# blackfin_b_flash_jtag_serial.net
KiCad netlist of a schematic drawn in Altium Designer
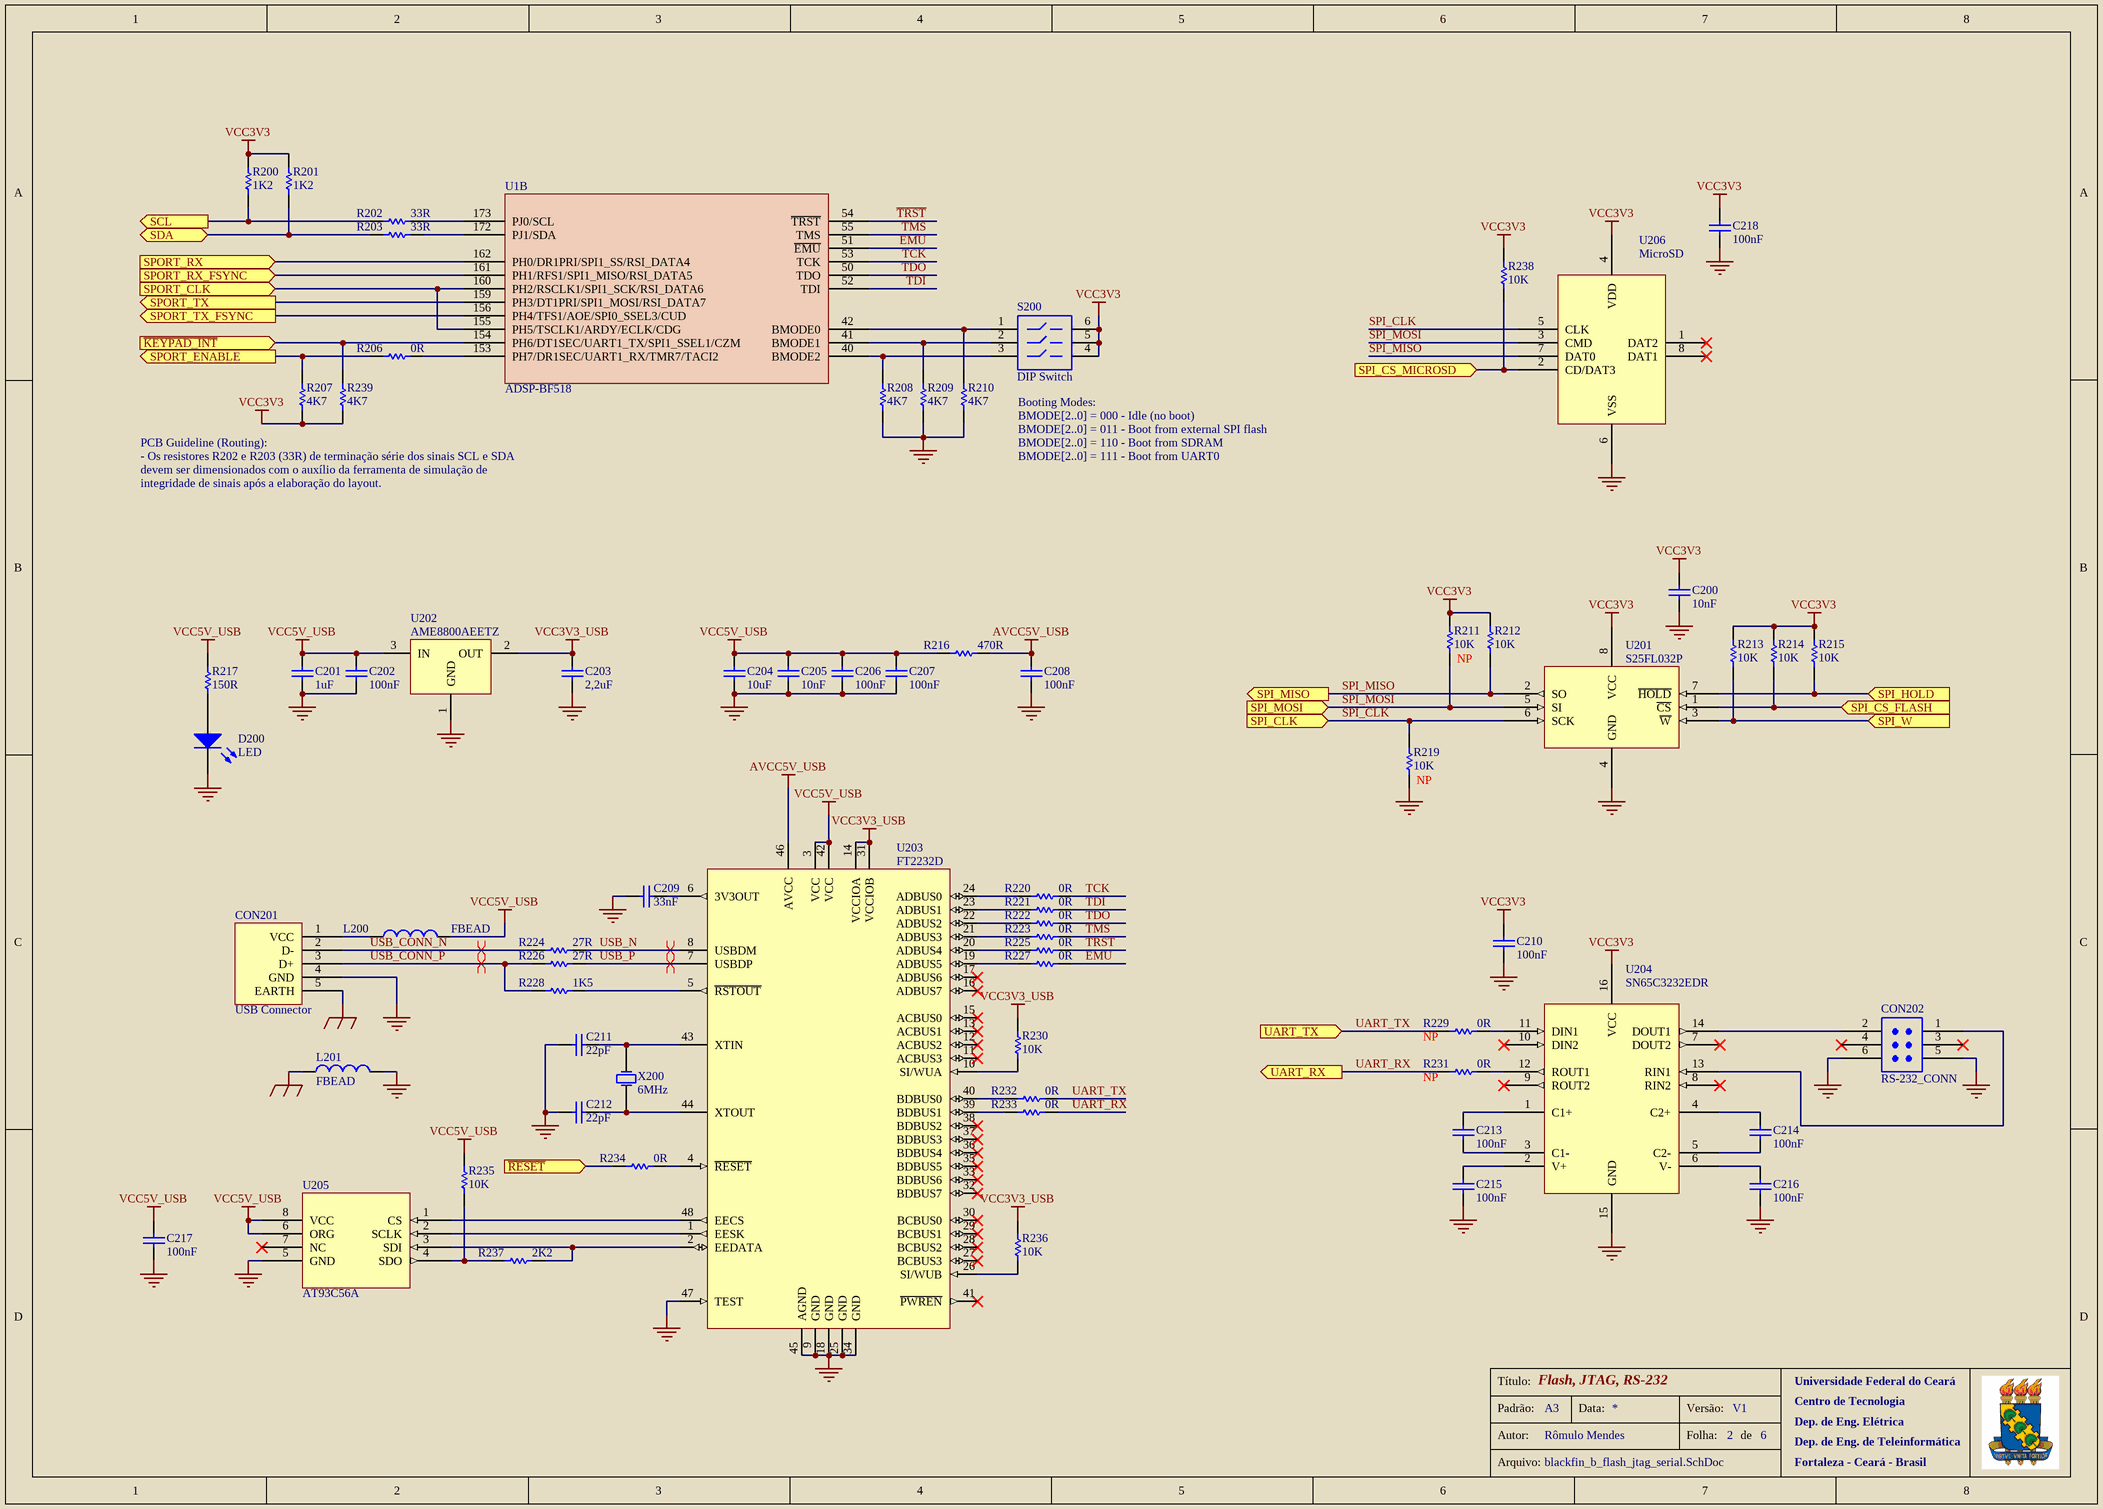
[diagram p0: blackfin_b_flash_jtag_serial.SchDoc]

(export (version "E")
  (design (tool "Eeschema 10.0.6"))
  (components
    (comp (ref "C200")
      (value "10nF")
      (footprint "blackfin_pcblib:C_0603")
      (fields
        (field (name "EVENDORPART#") "77-VJ0603Y103KXAPBC")
        (field (name "MANUFACTURER") "Vishay/Vitramon")
        (field (name "PART#") "VJ0603Y103KXAPW1BC")
      )
      (libsource (lib "blackfin_schlib") (part "Capacitor"))
    )
    (comp (ref "C201")
      (value "1uF")
      (footprint "blackfin_pcblib:C_0603")
      (fields
        (field (name "EVENDORPART#") "81-GRM188F51E105ZA12")
        (field (name "MANUFACTURER") "Murata")
        (field (name "PART#") "GRM188F51E105ZA12D")
      )
      (libsource (lib "blackfin_schlib") (part "Capacitor"))
    )
    (comp (ref "C202")
      (value "100nF")
      (footprint "blackfin_pcblib:C_0603")
      (fields
        (field (name "EVENDORPART#") "81-GRM188R71E104KA01")
        (field (name "MANUFACTURER") "Murata")
        (field (name "PART#") "GRM188R71E104KA01J")
      )
      (libsource (lib "blackfin_schlib") (part "Capacitor"))
    )
    (comp (ref "C203")
      (value "2,2uF")
      (footprint "blackfin_pcblib:C_0603")
      (fields
        (field (name "EVENDORPART#") "81-GRM188F51A225ZE01")
        (field (name "MANUFACTURER") "Murata")
        (field (name "PART#") "GRM188F51A225ZE01D")
      )
      (libsource (lib "blackfin_schlib") (part "Capacitor"))
    )
    (comp (ref "C204")
      (value "10uF")
      (footprint "blackfin_pcblib:C_0805")
      (fields
        (field (name "EVENDORPART#") "810-C2012Y5V1C106Z")
        (field (name "MANUFACTURER") "TDK")
        (field (name "PART#") "C2012Y5V1C106Z")
      )
      (libsource (lib "blackfin_schlib") (part "Capacitor"))
    )
    (comp (ref "C205")
      (value "10nF")
      (footprint "blackfin_pcblib:C_0603")
      (fields
        (field (name "EVENDORPART#") "77-VJ0603Y103KXAPBC")
        (field (name "MANUFACTURER") "Vishay/Vitramon")
        (field (name "PART#") "VJ0603Y103KXAPW1BC")
      )
      (libsource (lib "blackfin_schlib") (part "Capacitor"))
    )
    (comp (ref "C206")
      (value "100nF")
      (footprint "blackfin_pcblib:C_0603")
      (fields
        (field (name "EVENDORPART#") "81-GRM188R71E104KA01")
        (field (name "MANUFACTURER") "Murata")
        (field (name "PART#") "GRM188R71E104KA01J")
      )
      (libsource (lib "blackfin_schlib") (part "Capacitor"))
    )
    (comp (ref "C207")
      (value "100nF")
      (footprint "blackfin_pcblib:C_0603")
      (fields
        (field (name "EVENDORPART#") "81-GRM188R71E104KA01")
        (field (name "MANUFACTURER") "Murata")
        (field (name "PART#") "GRM188R71E104KA01J")
      )
      (libsource (lib "blackfin_schlib") (part "Capacitor"))
    )
    (comp (ref "C208")
      (value "100nF")
      (footprint "blackfin_pcblib:C_0603")
      (fields
        (field (name "EVENDORPART#") "81-GRM188R71E104KA01")
        (field (name "MANUFACTURER") "Murata")
        (field (name "PART#") "GRM188R71E104KA01J")
      )
      (libsource (lib "blackfin_schlib") (part "Capacitor"))
    )
    (comp (ref "C209")
      (value "33nF")
      (footprint "blackfin_pcblib:C_0603")
      (fields
        (field (name "EVENDORPART#") "81-GRM18B11E333KA01D")
        (field (name "MANUFACTURER") "Murata")
        (field (name "PART#") "GRM188B11E333KA01D")
      )
      (libsource (lib "blackfin_schlib") (part "Capacitor"))
    )
    (comp (ref "C210")
      (value "100nF")
      (footprint "blackfin_pcblib:C_0603")
      (fields
        (field (name "EVENDORPART#") "81-GRM188R71E104KA01")
        (field (name "MANUFACTURER") "Murata")
        (field (name "PART#") "GRM188R71E104KA01J")
      )
      (libsource (lib "blackfin_schlib") (part "Capacitor"))
    )
    (comp (ref "C211")
      (value "22pF")
      (footprint "blackfin_pcblib:C_0603")
      (fields
        (field (name "EVENDORPART#") "581-06035A220J")
        (field (name "MANUFACTURER") "AVX")
        (field (name "PART#") "06035A220JAT2A")
      )
      (libsource (lib "blackfin_schlib") (part "Capacitor"))
    )
    (comp (ref "C212")
      (value "22pF")
      (footprint "blackfin_pcblib:C_0603")
      (fields
        (field (name "EVENDORPART#") "581-06035A220J")
        (field (name "MANUFACTURER") "AVX")
        (field (name "PART#") "06035A220JAT2A")
      )
      (libsource (lib "blackfin_schlib") (part "Capacitor"))
    )
    (comp (ref "C213")
      (value "100nF")
      (footprint "blackfin_pcblib:C_0603")
      (fields
        (field (name "EVENDORPART#") "81-GRM188R71E104KA01")
        (field (name "MANUFACTURER") "Murata")
        (field (name "PART#") "GRM188R71E104KA01J")
      )
      (libsource (lib "blackfin_schlib") (part "Capacitor"))
    )
    (comp (ref "C214")
      (value "100nF")
      (footprint "blackfin_pcblib:C_0603")
      (fields
        (field (name "EVENDORPART#") "81-GRM188R71E104KA01")
        (field (name "MANUFACTURER") "Murata")
        (field (name "PART#") "GRM188R71E104KA01J")
      )
      (libsource (lib "blackfin_schlib") (part "Capacitor"))
    )
    (comp (ref "C215")
      (value "100nF")
      (footprint "blackfin_pcblib:C_0603")
      (fields
        (field (name "EVENDORPART#") "81-GRM188R71E104KA01")
        (field (name "MANUFACTURER") "Murata")
        (field (name "PART#") "GRM188R71E104KA01J")
      )
      (libsource (lib "blackfin_schlib") (part "Capacitor"))
    )
    (comp (ref "C216")
      (value "100nF")
      (footprint "blackfin_pcblib:C_0603")
      (fields
        (field (name "EVENDORPART#") "81-GRM188R71E104KA01")
        (field (name "MANUFACTURER") "Murata")
        (field (name "PART#") "GRM188R71E104KA01J")
      )
      (libsource (lib "blackfin_schlib") (part "Capacitor"))
    )
    (comp (ref "C217")
      (value "100nF")
      (footprint "blackfin_pcblib:C_0603")
      (fields
        (field (name "EVENDORPART#") "81-GRM188R71E104KA01")
        (field (name "MANUFACTURER") "Murata")
        (field (name "PART#") "GRM188R71E104KA01J")
      )
      (libsource (lib "blackfin_schlib") (part "Capacitor"))
    )
    (comp (ref "C218")
      (value "100nF")
      (footprint "blackfin_pcblib:C_0603")
      (fields
        (field (name "EVENDORPART#") "81-GRM188R71E104KA01")
        (field (name "MANUFACTURER") "Murata")
        (field (name "PART#") "GRM188R71E104KA01J")
      )
      (libsource (lib "blackfin_schlib") (part "Capacitor"))
    )
    (comp (ref "CON201")
      (value "USB Connector")
      (footprint "blackfin_pcblib:USB Connector")
      (fields
        (field (name "EVENDORPART#") "649-61729-0010BLF")
        (field (name "MANUFACTURER") "FCI")
        (field (name "PART#") "61729-0010BLF")
      )
      (libsource (lib "blackfin_schlib") (part "USB Connector"))
    )
    (comp (ref "CON202")
      (value "RS-232_CONN")
      (footprint "blackfin_pcblib:Header_2x3")
      (fields
        (field (name "PART#") "87759-0614")
        (field (name "EVENDORPART#") "538-87759-0614")
        (field (name "MANUFACTURER") "Molex")
      )
      (libsource (lib "blackfin_schlib") (part "RS-232 Connector"))
    )
    (comp (ref "D200")
      (value "LED")
      (footprint "blackfin_pcblib:LED_0603")
      (description "Red LED")
      (fields (field (name "EVENDORPART#") "638-QTLP600C2TR") (field (name "MANUFACTURER") "Everlight"))
      (libsource (lib "blackfin_schlib") (part "LED"))
    )
    (comp (ref "L200")
      (value "FBEAD")
      (footprint "blackfin_pcblib:L_0603")
      (fields
        (field (name "EVENDORPART#") "875-MI0603L301R-10")
        (field (name "MANUFACTURER") "Laird Technologies")
        (field (name "PART#") "MI0603L301R-10")
      )
      (libsource (lib "blackfin_schlib") (part "Inductor"))
    )
    (comp (ref "L201")
      (value "FBEAD")
      (footprint "blackfin_pcblib:L_0603")
      (fields
        (field (name "EVENDORPART#") "875-MI0603L301R-10")
        (field (name "MANUFACTURER") "Laird Technologies")
        (field (name "PART#") "MI0603L301R-10")
      )
      (libsource (lib "blackfin_schlib") (part "Inductor"))
    )
    (comp (ref "R200")
      (value "1K2")
      (footprint "blackfin_pcblib:R_0603")
      (fields
        (field (name "EVENDORPART#") "71-CRCW0603-1.2K-E3")
        (field (name "PART#") "CRCW06031K20FKEA")
        (field (name "MANUFACTURER") "Vishay/Dale")
      )
      (libsource (lib "blackfin_schlib") (part "Resistor"))
    )
    (comp (ref "R201")
      (value "1K2")
      (footprint "blackfin_pcblib:R_0603")
      (fields
        (field (name "EVENDORPART#") "71-CRCW0603-1.2K-E3")
        (field (name "PART#") "CRCW06031K20FKEA")
        (field (name "MANUFACTURER") "Vishay/Dale")
      )
      (libsource (lib "blackfin_schlib") (part "Resistor"))
    )
    (comp (ref "R202")
      (value "33R")
      (footprint "blackfin_pcblib:R_0402")
      (fields
        (field (name "EVENDORPART#") "71-CRCW0402J-33-E3")
        (field (name "PART#") "CRCW040233R0JNED")
        (field (name "MANUFACTURER") "Vishay/Dale")
      )
      (libsource (lib "blackfin_schlib") (part "Resistor"))
    )
    (comp (ref "R203")
      (value "33R")
      (footprint "blackfin_pcblib:R_0402")
      (fields
        (field (name "EVENDORPART#") "71-CRCW0402J-33-E3")
        (field (name "PART#") "CRCW040233R0JNED")
        (field (name "MANUFACTURER") "Vishay/Dale")
      )
      (libsource (lib "blackfin_schlib") (part "Resistor"))
    )
    (comp (ref "R206")
      (value "0R")
      (footprint "blackfin_pcblib:R_0603")
      (fields
        (field (name "EVENDORPART#") "71-CRCW06030000Z0EB")
        (field (name "PART#") "CRCW06030000Z0EB")
        (field (name "MANUFACTURER") "Vishay/Dale")
      )
      (libsource (lib "blackfin_schlib") (part "Resistor"))
    )
    (comp (ref "R207")
      (value "4K7")
      (footprint "blackfin_pcblib:R_0603")
      (fields
        (field (name "EVENDORPART#") "71-CRCW0603J-4.7K-E3")
        (field (name "PART#") "CRCW06034K70JNEA")
        (field (name "MANUFACTURER") "Vishay/Dale")
      )
      (libsource (lib "blackfin_schlib") (part "Resistor"))
    )
    (comp (ref "R208")
      (value "4K7")
      (footprint "blackfin_pcblib:R_0603")
      (fields
        (field (name "EVENDORPART#") "71-CRCW0603J-4.7K-E3")
        (field (name "PART#") "CRCW06034K70JNEA")
        (field (name "MANUFACTURER") "Vishay/Dale")
      )
      (libsource (lib "blackfin_schlib") (part "Resistor"))
    )
    (comp (ref "R209")
      (value "4K7")
      (footprint "blackfin_pcblib:R_0603")
      (fields
        (field (name "EVENDORPART#") "71-CRCW0603J-4.7K-E3")
        (field (name "PART#") "CRCW06034K70JNEA")
        (field (name "MANUFACTURER") "Vishay/Dale")
      )
      (libsource (lib "blackfin_schlib") (part "Resistor"))
    )
    (comp (ref "R210")
      (value "4K7")
      (footprint "blackfin_pcblib:R_0603")
      (fields
        (field (name "EVENDORPART#") "71-CRCW0603J-4.7K-E3")
        (field (name "PART#") "CRCW06034K70JNEA")
        (field (name "MANUFACTURER") "Vishay/Dale")
      )
      (libsource (lib "blackfin_schlib") (part "Resistor"))
    )
    (comp (ref "R211")
      (value "10K")
      (footprint "blackfin_pcblib:R_0603")
      (fields
        (field (name "EVENDORPART#") "71-CRCW0603-10K-E3")
        (field (name "PART#") "CRCW060310K0FKEA")
        (field (name "MANUFACTURER") "Vishay/Dale")
      )
      (libsource (lib "blackfin_schlib") (part "Resistor"))
    )
    (comp (ref "R212")
      (value "10K")
      (footprint "blackfin_pcblib:R_0603")
      (fields
        (field (name "EVENDORPART#") "71-CRCW0603-10K-E3")
        (field (name "PART#") "CRCW060310K0FKEA")
        (field (name "MANUFACTURER") "Vishay/Dale")
      )
      (libsource (lib "blackfin_schlib") (part "Resistor"))
    )
    (comp (ref "R213")
      (value "10K")
      (footprint "blackfin_pcblib:R_0603")
      (fields
        (field (name "EVENDORPART#") "71-CRCW0603-10K-E3")
        (field (name "PART#") "CRCW060310K0FKEA")
        (field (name "MANUFACTURER") "Vishay/Dale")
      )
      (libsource (lib "blackfin_schlib") (part "Resistor"))
    )
    (comp (ref "R214")
      (value "10K")
      (footprint "blackfin_pcblib:R_0603")
      (fields
        (field (name "EVENDORPART#") "71-CRCW0603-10K-E3")
        (field (name "PART#") "CRCW060310K0FKEA")
        (field (name "MANUFACTURER") "Vishay/Dale")
      )
      (libsource (lib "blackfin_schlib") (part "Resistor"))
    )
    (comp (ref "R215")
      (value "10K")
      (footprint "blackfin_pcblib:R_0603")
      (fields
        (field (name "EVENDORPART#") "71-CRCW0603-10K-E3")
        (field (name "PART#") "CRCW060310K0FKEA")
        (field (name "MANUFACTURER") "Vishay/Dale")
      )
      (libsource (lib "blackfin_schlib") (part "Resistor"))
    )
    (comp (ref "R216")
      (value "470R")
      (footprint "blackfin_pcblib:R_0603")
      (fields
        (field (name "EVENDORPART#") "71-CRCW0603-470-E3")
        (field (name "PART#") "CRCW0603470RFKEA")
        (field (name "MANUFACTURER") "Vishay/Dale")
      )
      (libsource (lib "blackfin_schlib") (part "Resistor"))
    )
    (comp (ref "R217")
      (value "150R")
      (footprint "blackfin_pcblib:R_0603")
      (fields
        (field (name "EVENDORPART#") "71-CRCW0603150RJNEB")
        (field (name "PART#") "CRCW0603150RJNEB")
        (field (name "MANUFACTURER") "Vishay/Dale")
      )
      (libsource (lib "blackfin_schlib") (part "Resistor"))
    )
    (comp (ref "R219")
      (value "10K")
      (footprint "blackfin_pcblib:R_0603")
      (fields
        (field (name "EVENDORPART#") "71-CRCW0603-10K-E3")
        (field (name "PART#") "CRCW060310K0FKEA")
        (field (name "MANUFACTURER") "Vishay/Dale")
      )
      (libsource (lib "blackfin_schlib") (part "Resistor"))
    )
    (comp (ref "R220")
      (value "0R")
      (footprint "blackfin_pcblib:R_0603")
      (fields
        (field (name "EVENDORPART#") "71-CRCW06030000Z0EB")
        (field (name "PART#") "CRCW06030000Z0EB")
        (field (name "MANUFACTURER") "Vishay/Dale")
      )
      (libsource (lib "blackfin_schlib") (part "Resistor"))
    )
    (comp (ref "R221")
      (value "0R")
      (footprint "blackfin_pcblib:R_0603")
      (fields
        (field (name "EVENDORPART#") "71-CRCW06030000Z0EB")
        (field (name "PART#") "CRCW06030000Z0EB")
        (field (name "MANUFACTURER") "Vishay/Dale")
      )
      (libsource (lib "blackfin_schlib") (part "Resistor"))
    )
    (comp (ref "R222")
      (value "0R")
      (footprint "blackfin_pcblib:R_0603")
      (fields
        (field (name "EVENDORPART#") "71-CRCW06030000Z0EB")
        (field (name "PART#") "CRCW06030000Z0EB")
        (field (name "MANUFACTURER") "Vishay/Dale")
      )
      (libsource (lib "blackfin_schlib") (part "Resistor"))
    )
    (comp (ref "R223")
      (value "0R")
      (footprint "blackfin_pcblib:R_0603")
      (fields
        (field (name "EVENDORPART#") "71-CRCW06030000Z0EB")
        (field (name "PART#") "CRCW06030000Z0EB")
        (field (name "MANUFACTURER") "Vishay/Dale")
      )
      (libsource (lib "blackfin_schlib") (part "Resistor"))
    )
    (comp (ref "R224")
      (value "27R")
      (footprint "blackfin_pcblib:R_0603")
      (fields
        (field (name "EVENDORPART#") "71-CRCW0603-27-E3")
        (field (name "PART#") "CRCW060327R0FKEA")
        (field (name "MANUFACTURER") "Vishay/Dale")
      )
      (libsource (lib "blackfin_schlib") (part "Resistor"))
    )
    (comp (ref "R225")
      (value "0R")
      (footprint "blackfin_pcblib:R_0603")
      (fields
        (field (name "EVENDORPART#") "71-CRCW06030000Z0EB")
        (field (name "PART#") "CRCW06030000Z0EB")
        (field (name "MANUFACTURER") "Vishay/Dale")
      )
      (libsource (lib "blackfin_schlib") (part "Resistor"))
    )
    (comp (ref "R226")
      (value "27R")
      (footprint "blackfin_pcblib:R_0603")
      (fields
        (field (name "EVENDORPART#") "71-CRCW0603-27-E3")
        (field (name "PART#") "CRCW060327R0FKEA")
        (field (name "MANUFACTURER") "Vishay/Dale")
      )
      (libsource (lib "blackfin_schlib") (part "Resistor"))
    )
    (comp (ref "R227")
      (value "0R")
      (footprint "blackfin_pcblib:R_0603")
      (fields
        (field (name "EVENDORPART#") "71-CRCW06030000Z0EB")
        (field (name "PART#") "CRCW06030000Z0EB")
        (field (name "MANUFACTURER") "Vishay/Dale")
      )
      (libsource (lib "blackfin_schlib") (part "Resistor"))
    )
    (comp (ref "R228")
      (value "1K5")
      (footprint "blackfin_pcblib:R_0603")
      (fields
        (field (name "EVENDORPART#") "71-CRCW0603-1.5K-E3")
        (field (name "PART#") "CRCW06031K50FKEA")
        (field (name "MANUFACTURER") "Vishay/Dale")
      )
      (libsource (lib "blackfin_schlib") (part "Resistor"))
    )
    (comp (ref "R229")
      (value "0R")
      (footprint "blackfin_pcblib:R_0603")
      (fields
        (field (name "EVENDORPART#") "71-CRCW06030000Z0EB")
        (field (name "PART#") "CRCW06030000Z0EB")
        (field (name "MANUFACTURER") "Vishay/Dale")
      )
      (libsource (lib "blackfin_schlib") (part "Resistor"))
    )
    (comp (ref "R230")
      (value "10K")
      (footprint "blackfin_pcblib:R_0603")
      (fields
        (field (name "EVENDORPART#") "71-CRCW0603-10K-E3")
        (field (name "PART#") "CRCW060310K0FKEA")
        (field (name "MANUFACTURER") "Vishay/Dale")
      )
      (libsource (lib "blackfin_schlib") (part "Resistor"))
    )
    (comp (ref "R231")
      (value "0R")
      (footprint "blackfin_pcblib:R_0603")
      (fields
        (field (name "EVENDORPART#") "71-CRCW06030000Z0EB")
        (field (name "PART#") "CRCW06030000Z0EB")
        (field (name "MANUFACTURER") "Vishay/Dale")
      )
      (libsource (lib "blackfin_schlib") (part "Resistor"))
    )
    (comp (ref "R232")
      (value "0R")
      (footprint "blackfin_pcblib:R_0603")
      (fields
        (field (name "EVENDORPART#") "71-CRCW06030000Z0EB")
        (field (name "PART#") "CRCW06030000Z0EB")
        (field (name "MANUFACTURER") "Vishay/Dale")
      )
      (libsource (lib "blackfin_schlib") (part "Resistor"))
    )
    (comp (ref "R233")
      (value "0R")
      (footprint "blackfin_pcblib:R_0603")
      (fields
        (field (name "EVENDORPART#") "71-CRCW06030000Z0EB")
        (field (name "PART#") "CRCW06030000Z0EB")
        (field (name "MANUFACTURER") "Vishay/Dale")
      )
      (libsource (lib "blackfin_schlib") (part "Resistor"))
    )
    (comp (ref "R234")
      (value "0R")
      (footprint "blackfin_pcblib:R_0603")
      (fields
        (field (name "EVENDORPART#") "71-CRCW06030000Z0EB")
        (field (name "PART#") "CRCW06030000Z0EB")
        (field (name "MANUFACTURER") "Vishay/Dale")
      )
      (libsource (lib "blackfin_schlib") (part "Resistor"))
    )
    (comp (ref "R235")
      (value "10K")
      (footprint "blackfin_pcblib:R_0603")
      (fields
        (field (name "EVENDORPART#") "71-CRCW0603-10K-E3")
        (field (name "PART#") "CRCW060310K0FKEA")
        (field (name "MANUFACTURER") "Vishay/Dale")
      )
      (libsource (lib "blackfin_schlib") (part "Resistor"))
    )
    (comp (ref "R236")
      (value "10K")
      (footprint "blackfin_pcblib:R_0603")
      (fields
        (field (name "EVENDORPART#") "71-CRCW0603-10K-E3")
        (field (name "PART#") "CRCW060310K0FKEA")
        (field (name "MANUFACTURER") "Vishay/Dale")
      )
      (libsource (lib "blackfin_schlib") (part "Resistor"))
    )
    (comp (ref "R237")
      (value "2K2")
      (footprint "blackfin_pcblib:R_0603")
      (fields
        (field (name "EVENDORPART#") "71-CRCW06032K20JNEB")
        (field (name "PART#") "CRCW06032K20JNEB")
        (field (name "MANUFACTURER") "Vishay/Dale")
      )
      (libsource (lib "blackfin_schlib") (part "Resistor"))
    )
    (comp (ref "R238")
      (value "10K")
      (footprint "blackfin_pcblib:R_0603")
      (fields
        (field (name "EVENDORPART#") "71-CRCW0603-10K-E3")
        (field (name "PART#") "CRCW060310K0FKEA")
        (field (name "MANUFACTURER") "Vishay/Dale")
      )
      (libsource (lib "blackfin_schlib") (part "Resistor"))
    )
    (comp (ref "R239")
      (value "4K7")
      (footprint "blackfin_pcblib:R_0603")
      (fields
        (field (name "EVENDORPART#") "71-CRCW0603J-4.7K-E3")
        (field (name "PART#") "CRCW06034K70JNEA")
        (field (name "MANUFACTURER") "Vishay/Dale")
      )
      (libsource (lib "blackfin_schlib") (part "Resistor"))
    )
    (comp (ref "S200")
      (value "DIP Switch")
      (footprint "blackfin_pcblib:DIP Switch")
      (fields
        (field (name "EVENDORPART#") "611-SDA03H1SBD")
        (field (name "MANUFACTURER") "C&K Components")
        (field (name "PART#") "SDA03H1SBD")
      )
      (libsource (lib "*") (part "DIP Switch"))
    )
    (comp (ref "U1")
      (value "ADSP-BF518")
      (footprint "blackfin_pcblib:LQFP-176")
      (fields (field (name "EVENDORPART#") "ADSP-BF518BSWZ-4") (field (name "MANUFACTURER") "Analog Devices"))
      (libsource (lib "blackfin_schlib") (part "ADSP-BF518"))
    )
    (comp (ref "U201")
      (value "S25FL032P")
      (footprint "blackfin_pcblib:SO-8")
      (fields (field (name "PART#") "S25FL032P0XMFI010") (field (name "MANUFACTURER") "Spansion"))
      (libsource (lib "blackfin_schlib") (part "S25FL032P"))
    )
    (comp (ref "U202")
      (value "AME8800AEETZ")
      (footprint "blackfin_pcblib:SOT-23")
      (fields (field (name "EVENDORPART#") "827-AME8800AEETZ") (field (name "MANUFACTURER") "AME"))
      (libsource (lib "blackfin_schlib") (part "AME8800AEETZ"))
    )
    (comp (ref "U203")
      (value "FT2232D")
      (footprint "blackfin_pcblib:LQFP-48")
      (fields (field (name "EVENDORPART#") "895-FT2232D") (field (name "MANUFACTURER") "FTDI"))
      (libsource (lib "blackfin_schlib") (part "FT2232D"))
    )
    (comp (ref "U204")
      (value "SN65C3232EDR")
      (footprint "blackfin_pcblib:SOIC-16")
      (fields
        (field (name "EVENDORPART#") "595-SN65C3232EDR")
        (field (name "MANUFACTURER") "Texas Instruments")
      )
      (libsource (lib "blackfin_schlib") (part "RS-232 Transceiver"))
    )
    (comp (ref "U205")
      (value "AT93C56A")
      (footprint "blackfin_pcblib:SOIC-8 (AT93C56A)")
      (fields
        (field (name "EVENDORPART#") "556-A93C56A10SU2.7")
        (field (name "MANUFACTURER") "Atmel")
        (field (name "PART#") "AT93C56A-10SU-2.7")
      )
      (libsource (lib "blackfin_schlib") (part "AT93C56A"))
    )
    (comp (ref "U206")
      (value "MicroSD")
      (footprint "blackfin_pcblib:MICRO_SD")
      (fields
        (field (name "MANUFACTURER") "AVX Corporation")
        (field (name "PART#") "045138008010890+")
        (field (name "EVENDORPART#") "478-4965-1-ND")
      )
      (libsource (lib "blackfin_schlib") (part "MicroSD"))
    )
    (comp (ref "X200")
      (value "6MHz")
      (footprint "blackfin_pcblib:XTAL_6MHz")
      (fields
        (field (name "EVENDORPART#") "774-ATS060SM-1")
        (field (name "PART#") "ATS060SM-1")
        (field (name "MANUFACTURER") "CTS Electronic Components")
      )
      (libsource (lib "blackfin_schlib") (part "XTAL"))
    )
  )
  (nets
    (net (code "1") (name "/SCL") (class "Default")
      (node (ref "R200") (pin "1") (pinfunction "1_1") (pintype "passive"))
      (node (ref "R202") (pin "1") (pinfunction "1_1") (pintype "passive"))
    )
    (net (code "2") (name "/SDA") (class "Default")
      (node (ref "R201") (pin "1") (pinfunction "1_1") (pintype "passive"))
      (node (ref "R203") (pin "1") (pinfunction "1_1") (pintype "passive"))
    )
    (net (code "3") (name "/SPI_CLK") (class "Default")
      (node (ref "R219") (pin "2") (pinfunction "2_2") (pintype "passive"))
      (node (ref "U201") (pin "6") (pinfunction "SCK_6") (pintype "input"))
      (node (ref "U206") (pin "5") (pinfunction "CLK_5") (pintype "passive"))
    )
    (net (code "4") (name "/SPI_CS_FLASH") (class "Default")
      (node (ref "R214") (pin "1") (pinfunction "1_1") (pintype "passive"))
      (node (ref "U201") (pin "1") (pinfunction "~{CS}_1") (pintype "input"))
    )
    (net (code "5") (name "/SPI_CS_MICROSD") (class "Default")
      (node (ref "R238") (pin "1") (pinfunction "1_1") (pintype "passive"))
      (node (ref "U206") (pin "2") (pinfunction "CD/DAT3_2") (pintype "passive"))
    )
    (net (code "6") (name "/SPI_HOLD") (class "Default")
      (node (ref "R215") (pin "1") (pinfunction "1_1") (pintype "passive"))
      (node (ref "U201") (pin "7") (pinfunction "~{HOLD}_7") (pintype "input"))
    )
    (net (code "7") (name "/SPI_MISO") (class "Default")
      (node (ref "R212") (pin "1") (pinfunction "1_1") (pintype "passive"))
      (node (ref "U201") (pin "2") (pinfunction "SO_2") (pintype "output"))
      (node (ref "U206") (pin "7") (pinfunction "DAT0_7") (pintype "passive"))
    )
    (net (code "8") (name "/SPI_MOSI") (class "Default")
      (node (ref "R211") (pin "1") (pinfunction "1_1") (pintype "passive"))
      (node (ref "U201") (pin "5") (pinfunction "SI_5") (pintype "input"))
      (node (ref "U206") (pin "3") (pinfunction "CMD_3") (pintype "passive"))
    )
    (net (code "9") (name "/SPI_W") (class "Default")
      (node (ref "R213") (pin "1") (pinfunction "1_1") (pintype "passive"))
      (node (ref "U201") (pin "3") (pinfunction "~{W}_3") (pintype "input"))
    )
    (net (code "10") (name "/SPORT_CLK") (class "Default")
      (node (ref "U1") (pin "155") (pinfunction "PH5/TSCLK1/ARDY/ECLK/CDG_155") (pintype "passive"))
      (node (ref "U1") (pin "160") (pinfunction "PH2/RSCLK1/SPI1_SCK/RSI_DATA6_160") (pintype "passive"))
    )
    (net (code "11") (name "/SPORT_ENABLE") (class "Default")
      (node (ref "R206") (pin "1") (pinfunction "1_1") (pintype "passive"))
      (node (ref "R207") (pin "2") (pinfunction "2_2") (pintype "passive"))
    )
    (net (code "12") (name "/SPORT_RX") (class "Default")
      (node (ref "U1") (pin "162") (pinfunction "PH0/DR1PRI/SPI1_SS/RSI_DATA4_162") (pintype "passive"))
    )
    (net (code "13") (name "/SPORT_RX_FSYNC") (class "Default")
      (node (ref "U1") (pin "161") (pinfunction "PH1/RFS1/SPI1_MISO/RSI_DATA5_161") (pintype "passive"))
    )
    (net (code "14") (name "/SPORT_TX") (class "Default")
      (node (ref "U1") (pin "159") (pinfunction "PH3/DT1PRI/SPI1_MOSI/RSI_DATA7_159") (pintype "passive"))
    )
    (net (code "15") (name "/SPORT_TX_FSYNC") (class "Default")
      (node (ref "U1") (pin "156") (pinfunction "PH4/TFS1/AOE/SPI0_SSEL3/CUD_156") (pintype "passive"))
    )
    (net (code "16") (name "/TCK") (class "Default")
      (node (ref "R220") (pin "2") (pinfunction "2_2") (pintype "passive"))
      (node (ref "U1") (pin "53") (pinfunction "TCK_53") (pintype "passive"))
    )
    (net (code "17") (name "/TDI") (class "Default")
      (node (ref "R221") (pin "2") (pinfunction "2_2") (pintype "passive"))
      (node (ref "U1") (pin "52") (pinfunction "TDI_52") (pintype "passive"))
    )
    (net (code "18") (name "/TDO") (class "Default")
      (node (ref "R222") (pin "2") (pinfunction "2_2") (pintype "passive"))
      (node (ref "U1") (pin "50") (pinfunction "TDO_50") (pintype "passive"))
    )
    (net (code "19") (name "/TMS") (class "Default")
      (node (ref "R223") (pin "2") (pinfunction "2_2") (pintype "passive"))
      (node (ref "U1") (pin "55") (pinfunction "TMS_55") (pintype "passive"))
    )
    (net (code "20") (name "/UART_RX") (class "Default")
      (node (ref "R231") (pin "1") (pinfunction "1_1") (pintype "passive"))
      (node (ref "R233") (pin "2") (pinfunction "2_2") (pintype "passive"))
    )
    (net (code "21") (name "/UART_TX") (class "Default")
      (node (ref "R229") (pin "1") (pinfunction "1_1") (pintype "passive"))
      (node (ref "R232") (pin "2") (pinfunction "2_2") (pintype "passive"))
    )
    (net (code "22") (name "/USB_CONN_N") (class "Default")
      (node (ref "CON201") (pin "2") (pinfunction "D-_2") (pintype "passive"))
      (node (ref "R224") (pin "1") (pinfunction "1_1") (pintype "passive"))
    )
    (net (code "23") (name "/USB_CONN_P") (class "Default")
      (node (ref "CON201") (pin "3") (pinfunction "D+_3") (pintype "passive"))
      (node (ref "R226") (pin "1") (pinfunction "1_1") (pintype "passive"))
      (node (ref "R228") (pin "1") (pinfunction "1_1") (pintype "passive"))
    )
    (net (code "24") (name "/USB_N") (class "Default")
      (node (ref "R224") (pin "2") (pinfunction "2_2") (pintype "passive"))
      (node (ref "U203") (pin "8") (pinfunction "USBDM_8") (pintype "passive"))
    )
    (net (code "25") (name "/USB_P") (class "Default")
      (node (ref "R226") (pin "2") (pinfunction "2_2") (pintype "passive"))
      (node (ref "U203") (pin "7") (pinfunction "USBDP_7") (pintype "passive"))
    )
    (net (code "26") (name "/~{EMU}") (class "Default")
      (node (ref "R227") (pin "2") (pinfunction "2_2") (pintype "passive"))
      (node (ref "U1") (pin "51") (pinfunction "~{EMU}_51") (pintype "passive"))
    )
    (net (code "27") (name "/~{KEYPAD_INT}") (class "Default")
      (node (ref "R239") (pin "2") (pinfunction "2_2") (pintype "passive"))
      (node (ref "U1") (pin "154") (pinfunction "PH6/DT1SEC/UART1_TX/SPI1_SSEL1/CZM_154") (pintype "passive"))
    )
    (net (code "28") (name "/~{RESET}") (class "Default")
      (node (ref "R234") (pin "1") (pinfunction "1_1") (pintype "passive"))
    )
    (net (code "29") (name "/~{TRST}") (class "Default")
      (node (ref "R225") (pin "2") (pinfunction "2_2") (pintype "passive"))
      (node (ref "U1") (pin "54") (pinfunction "~{TRST}_54") (pintype "passive"))
    )
    (net (code "30") (name "AVCC5V_USB") (class "Default")
      (node (ref "C208") (pin "2") (pinfunction "2_2") (pintype "passive"))
      (node (ref "R216") (pin "2") (pinfunction "2_2") (pintype "passive"))
      (node (ref "U203") (pin "46") (pinfunction "AVCC_46") (pintype "power_in"))
    )
    (net (code "31") (name "EARTH") (class "Default")
      (node (ref "CON201") (pin "5") (pinfunction "EARTH_5") (pintype "passive"))
      (node (ref "L201") (pin "1") (pinfunction "1_1") (pintype "passive"))
    )
    (net (code "32") (name "GND") (class "Default")
      (node (ref "C200") (pin "1") (pinfunction "1_1") (pintype "passive"))
      (node (ref "C201") (pin "1") (pinfunction "1_1") (pintype "passive"))
      (node (ref "C202") (pin "1") (pinfunction "1_1") (pintype "passive"))
      (node (ref "C203") (pin "1") (pinfunction "1_1") (pintype "passive"))
      (node (ref "C204") (pin "1") (pinfunction "1_1") (pintype "passive"))
      (node (ref "C205") (pin "1") (pinfunction "1_1") (pintype "passive"))
      (node (ref "C206") (pin "1") (pinfunction "1_1") (pintype "passive"))
      (node (ref "C207") (pin "1") (pinfunction "1_1") (pintype "passive"))
      (node (ref "C208") (pin "1") (pinfunction "1_1") (pintype "passive"))
      (node (ref "C209") (pin "2") (pinfunction "2_2") (pintype "passive"))
      (node (ref "C210") (pin "1") (pinfunction "1_1") (pintype "passive"))
      (node (ref "C211") (pin "2") (pinfunction "2_2") (pintype "passive"))
      (node (ref "C212") (pin "2") (pinfunction "2_2") (pintype "passive"))
      (node (ref "C215") (pin "1") (pinfunction "1_1") (pintype "passive"))
      (node (ref "C216") (pin "1") (pinfunction "1_1") (pintype "passive"))
      (node (ref "C217") (pin "1") (pinfunction "1_1") (pintype "passive"))
      (node (ref "C218") (pin "1") (pinfunction "1_1") (pintype "passive"))
      (node (ref "CON201") (pin "4") (pinfunction "GND_4") (pintype "passive"))
      (node (ref "CON202") (pin "5") (pinfunction "GND_5") (pintype "passive"))
      (node (ref "CON202") (pin "6") (pinfunction "GND_6") (pintype "passive"))
      (node (ref "D200") (pin "2") (pinfunction "K_2") (pintype "passive"))
      (node (ref "L201") (pin "2") (pinfunction "2_2") (pintype "passive"))
      (node (ref "R208") (pin "1") (pinfunction "1_1") (pintype "passive"))
      (node (ref "R209") (pin "1") (pinfunction "1_1") (pintype "passive"))
      (node (ref "R210") (pin "1") (pinfunction "1_1") (pintype "passive"))
      (node (ref "R219") (pin "1") (pinfunction "1_1") (pintype "passive"))
      (node (ref "U201") (pin "4") (pinfunction "GND_4") (pintype "power_in"))
      (node (ref "U202") (pin "1") (pinfunction "GND_1") (pintype "passive"))
      (node (ref "U203") (pin "18") (pinfunction "GND_18") (pintype "power_in"))
      (node (ref "U203") (pin "25") (pinfunction "GND_25") (pintype "power_in"))
      (node (ref "U203") (pin "34") (pinfunction "GND_34") (pintype "power_in"))
      (node (ref "U203") (pin "45") (pinfunction "AGND_45") (pintype "power_in"))
      (node (ref "U203") (pin "47") (pinfunction "TEST_47") (pintype "input"))
      (node (ref "U203") (pin "9") (pinfunction "GND_9") (pintype "power_in"))
      (node (ref "U204") (pin "15") (pinfunction "GND_15") (pintype "power_in"))
      (node (ref "U205") (pin "5") (pinfunction "GND_5") (pintype "power_in"))
      (node (ref "U206") (pin "6") (pinfunction "VSS_6") (pintype "passive"))
    )
    (net (code "33") (name "Net-(CON201-VCC)") (class "Default")
      (node (ref "CON201") (pin "1") (pinfunction "VCC_1") (pintype "passive"))
      (node (ref "L200") (pin "1") (pinfunction "1_1") (pintype "passive"))
    )
    (net (code "34") (name "Net-(CON202-RX)") (class "Default")
      (node (ref "CON202") (pin "2") (pinfunction "RX_2") (pintype "passive"))
      (node (ref "U204") (pin "14") (pinfunction "DOUT1_14") (pintype "output"))
    )
    (net (code "35") (name "Net-(CON202-TX)") (class "Default")
      (node (ref "CON202") (pin "1") (pinfunction "TX_1") (pintype "passive"))
      (node (ref "U204") (pin "13") (pinfunction "RIN1_13") (pintype "input"))
    )
    (net (code "36") (name "Net-(D200-A)") (class "Default")
      (node (ref "D200") (pin "1") (pinfunction "A_1") (pintype "passive"))
      (node (ref "R217") (pin "1") (pinfunction "1_1") (pintype "passive"))
    )
    (net (code "37") (name "Net-(U1B-BMODE0)") (class "Default")
      (node (ref "R210") (pin "2") (pinfunction "2_2") (pintype "passive"))
      (node (ref "S200") (pin "1") (pinfunction "1_1") (pintype "passive"))
      (node (ref "U1") (pin "42") (pinfunction "BMODE0_42") (pintype "passive"))
    )
    (net (code "38") (name "Net-(U1B-BMODE1)") (class "Default")
      (node (ref "R209") (pin "2") (pinfunction "2_2") (pintype "passive"))
      (node (ref "S200") (pin "2") (pinfunction "2_2") (pintype "passive"))
      (node (ref "U1") (pin "41") (pinfunction "BMODE1_41") (pintype "passive"))
    )
    (net (code "39") (name "Net-(U1B-BMODE2)") (class "Default")
      (node (ref "R208") (pin "2") (pinfunction "2_2") (pintype "passive"))
      (node (ref "S200") (pin "3") (pinfunction "3_3") (pintype "passive"))
      (node (ref "U1") (pin "40") (pinfunction "BMODE2_40") (pintype "passive"))
    )
    (net (code "40") (name "Net-(U1B-PH7{slash}DR1SEC{slash}UART1_RX{slash}TMR7{slash}TACI2)") (class "Default")
      (node (ref "R206") (pin "2") (pinfunction "2_2") (pintype "passive"))
      (node (ref "U1") (pin "153") (pinfunction "PH7/DR1SEC/UART1_RX/TMR7/TACI2_153") (pintype "passive"))
    )
    (net (code "41") (name "Net-(U1B-PJ0{slash}SCL)") (class "Default")
      (node (ref "R202") (pin "2") (pinfunction "2_2") (pintype "passive"))
      (node (ref "U1") (pin "173") (pinfunction "PJ0/SCL_173") (pintype "passive"))
    )
    (net (code "42") (name "Net-(U1B-PJ1{slash}SDA)") (class "Default")
      (node (ref "R203") (pin "2") (pinfunction "2_2") (pintype "passive"))
      (node (ref "U1") (pin "172") (pinfunction "PJ1/SDA_172") (pintype "passive"))
    )
    (net (code "43") (name "Net-(U203-3V3OUT)") (class "Default")
      (node (ref "C209") (pin "1") (pinfunction "1_1") (pintype "passive"))
      (node (ref "U203") (pin "6") (pinfunction "3V3OUT_6") (pintype "output"))
    )
    (net (code "44") (name "Net-(U203-ADBUS0)") (class "Default")
      (node (ref "R220") (pin "1") (pinfunction "1_1") (pintype "passive"))
      (node (ref "U203") (pin "24") (pinfunction "ADBUS0_24") (pintype "bidirectional"))
    )
    (net (code "45") (name "Net-(U203-ADBUS1)") (class "Default")
      (node (ref "R221") (pin "1") (pinfunction "1_1") (pintype "passive"))
      (node (ref "U203") (pin "23") (pinfunction "ADBUS1_23") (pintype "bidirectional"))
    )
    (net (code "46") (name "Net-(U203-ADBUS2)") (class "Default")
      (node (ref "R222") (pin "1") (pinfunction "1_1") (pintype "passive"))
      (node (ref "U203") (pin "22") (pinfunction "ADBUS2_22") (pintype "bidirectional"))
    )
    (net (code "47") (name "Net-(U203-ADBUS3)") (class "Default")
      (node (ref "R223") (pin "1") (pinfunction "1_1") (pintype "passive"))
      (node (ref "U203") (pin "21") (pinfunction "ADBUS3_21") (pintype "bidirectional"))
    )
    (net (code "48") (name "Net-(U203-ADBUS4)") (class "Default")
      (node (ref "R225") (pin "1") (pinfunction "1_1") (pintype "passive"))
      (node (ref "U203") (pin "20") (pinfunction "ADBUS4_20") (pintype "bidirectional"))
    )
    (net (code "49") (name "Net-(U203-ADBUS5)") (class "Default")
      (node (ref "R227") (pin "1") (pinfunction "1_1") (pintype "passive"))
      (node (ref "U203") (pin "19") (pinfunction "ADBUS5_19") (pintype "bidirectional"))
    )
    (net (code "50") (name "Net-(U203-BDBUS0)") (class "Default")
      (node (ref "R232") (pin "1") (pinfunction "1_1") (pintype "passive"))
      (node (ref "U203") (pin "40") (pinfunction "BDBUS0_40") (pintype "bidirectional"))
    )
    (net (code "51") (name "Net-(U203-BDBUS1)") (class "Default")
      (node (ref "R233") (pin "1") (pinfunction "1_1") (pintype "passive"))
      (node (ref "U203") (pin "39") (pinfunction "BDBUS1_39") (pintype "bidirectional"))
    )
    (net (code "52") (name "Net-(U203-EECS)") (class "Default")
      (node (ref "U203") (pin "48") (pinfunction "EECS_48") (pintype "output"))
      (node (ref "U205") (pin "1") (pinfunction "CS_1") (pintype "input"))
    )
    (net (code "53") (name "Net-(U203-EEDATA)") (class "Default")
      (node (ref "R237") (pin "1") (pinfunction "1_1") (pintype "passive"))
      (node (ref "U203") (pin "2") (pinfunction "EEDATA_2") (pintype "bidirectional"))
      (node (ref "U205") (pin "3") (pinfunction "SDI_3") (pintype "input"))
    )
    (net (code "54") (name "Net-(U203-EESK)") (class "Default")
      (node (ref "U203") (pin "1") (pinfunction "EESK_1") (pintype "output"))
      (node (ref "U205") (pin "2") (pinfunction "SCLK_2") (pintype "input"))
    )
    (net (code "55") (name "Net-(U203-SI{slash}WUA)") (class "Default")
      (node (ref "R230") (pin "2") (pinfunction "2_2") (pintype "passive"))
      (node (ref "U203") (pin "10") (pinfunction "SI/WUA_10") (pintype "input"))
    )
    (net (code "56") (name "Net-(U203-SI{slash}WUB)") (class "Default")
      (node (ref "R236") (pin "2") (pinfunction "2_2") (pintype "passive"))
      (node (ref "U203") (pin "26") (pinfunction "SI/WUB_26") (pintype "input"))
    )
    (net (code "57") (name "Net-(U203-XTIN)") (class "Default")
      (node (ref "C211") (pin "1") (pinfunction "1_1") (pintype "passive"))
      (node (ref "U203") (pin "43") (pinfunction "XTIN_43") (pintype "passive"))
      (node (ref "X200") (pin "2") (pinfunction "OSC2_2") (pintype "passive"))
    )
    (net (code "58") (name "Net-(U203-XTOUT)") (class "Default")
      (node (ref "C212") (pin "1") (pinfunction "1_1") (pintype "passive"))
      (node (ref "U203") (pin "44") (pinfunction "XTOUT_44") (pintype "passive"))
      (node (ref "X200") (pin "1") (pinfunction "OSC1_1") (pintype "passive"))
    )
    (net (code "59") (name "Net-(U203-~{RESET})") (class "Default")
      (node (ref "R234") (pin "2") (pinfunction "2_2") (pintype "passive"))
      (node (ref "U203") (pin "4") (pinfunction "~{RESET}_4") (pintype "input"))
    )
    (net (code "60") (name "Net-(U203-~{RSTOUT})") (class "Default")
      (node (ref "R228") (pin "2") (pinfunction "2_2") (pintype "passive"))
      (node (ref "U203") (pin "5") (pinfunction "~{RSTOUT}_5") (pintype "output"))
    )
    (net (code "61") (name "Net-(U204-C1+)") (class "Default")
      (node (ref "C213") (pin "2") (pinfunction "2_2") (pintype "passive"))
      (node (ref "U204") (pin "1") (pinfunction "C1+_1") (pintype "power_in"))
    )
    (net (code "62") (name "Net-(U204-C1-)") (class "Default")
      (node (ref "C213") (pin "1") (pinfunction "1_1") (pintype "passive"))
      (node (ref "U204") (pin "3") (pinfunction "C1-_3") (pintype "power_in"))
    )
    (net (code "63") (name "Net-(U204-C2+)") (class "Default")
      (node (ref "C214") (pin "2") (pinfunction "2_2") (pintype "passive"))
      (node (ref "U204") (pin "4") (pinfunction "C2+_4") (pintype "power_in"))
    )
    (net (code "64") (name "Net-(U204-C2-)") (class "Default")
      (node (ref "C214") (pin "1") (pinfunction "1_1") (pintype "passive"))
      (node (ref "U204") (pin "5") (pinfunction "C2-_5") (pintype "power_in"))
    )
    (net (code "65") (name "Net-(U204-DIN1)") (class "Default")
      (node (ref "R229") (pin "2") (pinfunction "2_2") (pintype "passive"))
      (node (ref "U204") (pin "11") (pinfunction "DIN1_11") (pintype "input"))
    )
    (net (code "66") (name "Net-(U204-ROUT1)") (class "Default")
      (node (ref "R231") (pin "2") (pinfunction "2_2") (pintype "passive"))
      (node (ref "U204") (pin "12") (pinfunction "ROUT1_12") (pintype "output"))
    )
    (net (code "67") (name "Net-(U204-V+)") (class "Default")
      (node (ref "C215") (pin "2") (pinfunction "2_2") (pintype "passive"))
      (node (ref "U204") (pin "2") (pinfunction "V+_2") (pintype "power_in"))
    )
    (net (code "68") (name "Net-(U204-V-)") (class "Default")
      (node (ref "C216") (pin "2") (pinfunction "2_2") (pintype "passive"))
      (node (ref "U204") (pin "6") (pinfunction "V-_6") (pintype "power_in"))
    )
    (net (code "69") (name "Net-(U205-SDO)") (class "Default")
      (node (ref "R235") (pin "1") (pinfunction "1_1") (pintype "passive"))
      (node (ref "R237") (pin "2") (pinfunction "2_2") (pintype "passive"))
      (node (ref "U205") (pin "4") (pinfunction "SDO_4") (pintype "output"))
    )
    (net (code "70") (name "VCC3V3") (class "Default")
      (node (ref "C200") (pin "2") (pinfunction "2_2") (pintype "passive"))
      (node (ref "C210") (pin "2") (pinfunction "2_2") (pintype "passive"))
      (node (ref "C218") (pin "2") (pinfunction "2_2") (pintype "passive"))
      (node (ref "R200") (pin "2") (pinfunction "2_2") (pintype "passive"))
      (node (ref "R201") (pin "2") (pinfunction "2_2") (pintype "passive"))
      (node (ref "R207") (pin "1") (pinfunction "1_1") (pintype "passive"))
      (node (ref "R211") (pin "2") (pinfunction "2_2") (pintype "passive"))
      (node (ref "R212") (pin "2") (pinfunction "2_2") (pintype "passive"))
      (node (ref "R213") (pin "2") (pinfunction "2_2") (pintype "passive"))
      (node (ref "R214") (pin "2") (pinfunction "2_2") (pintype "passive"))
      (node (ref "R215") (pin "2") (pinfunction "2_2") (pintype "passive"))
      (node (ref "R238") (pin "2") (pinfunction "2_2") (pintype "passive"))
      (node (ref "R239") (pin "1") (pinfunction "1_1") (pintype "passive"))
      (node (ref "S200") (pin "4") (pinfunction "4_4") (pintype "passive"))
      (node (ref "S200") (pin "5") (pinfunction "5_5") (pintype "passive"))
      (node (ref "S200") (pin "6") (pinfunction "6_6") (pintype "passive"))
      (node (ref "U201") (pin "8") (pinfunction "VCC_8") (pintype "power_in"))
      (node (ref "U204") (pin "16") (pinfunction "VCC_16") (pintype "power_in"))
      (node (ref "U206") (pin "4") (pinfunction "VDD_4") (pintype "passive"))
    )
    (net (code "71") (name "VCC3V3_USB") (class "Default")
      (node (ref "C203") (pin "2") (pinfunction "2_2") (pintype "passive"))
      (node (ref "R230") (pin "1") (pinfunction "1_1") (pintype "passive"))
      (node (ref "R236") (pin "1") (pinfunction "1_1") (pintype "passive"))
      (node (ref "U202") (pin "2") (pinfunction "OUT_2") (pintype "passive"))
      (node (ref "U203") (pin "14") (pinfunction "VCCIOA_14") (pintype "power_in"))
      (node (ref "U203") (pin "31") (pinfunction "VCCIOB_31") (pintype "power_in"))
    )
    (net (code "72") (name "VCC5V_USB") (class "Default")
      (node (ref "C201") (pin "2") (pinfunction "2_2") (pintype "passive"))
      (node (ref "C202") (pin "2") (pinfunction "2_2") (pintype "passive"))
      (node (ref "C204") (pin "2") (pinfunction "2_2") (pintype "passive"))
      (node (ref "C205") (pin "2") (pinfunction "2_2") (pintype "passive"))
      (node (ref "C206") (pin "2") (pinfunction "2_2") (pintype "passive"))
      (node (ref "C207") (pin "2") (pinfunction "2_2") (pintype "passive"))
      (node (ref "C217") (pin "2") (pinfunction "2_2") (pintype "passive"))
      (node (ref "L200") (pin "2") (pinfunction "2_2") (pintype "passive"))
      (node (ref "R216") (pin "1") (pinfunction "1_1") (pintype "passive"))
      (node (ref "R217") (pin "2") (pinfunction "2_2") (pintype "passive"))
      (node (ref "R235") (pin "2") (pinfunction "2_2") (pintype "passive"))
      (node (ref "U202") (pin "3") (pinfunction "IN_3") (pintype "passive"))
      (node (ref "U203") (pin "3") (pinfunction "VCC_3") (pintype "power_in"))
      (node (ref "U203") (pin "42") (pinfunction "VCC_42") (pintype "power_in"))
      (node (ref "U205") (pin "6") (pinfunction "ORG_6") (pintype "passive"))
      (node (ref "U205") (pin "8") (pinfunction "VCC_8") (pintype "power_in"))
    )
    (net (code "73") (name "unconnected-(CON202-NC-Pad3)") (class "Default")
      (node (ref "CON202") (pin "3") (pinfunction "NC_3") (pintype "passive+no_connect"))
    )
    (net (code "74") (name "unconnected-(CON202-NC-Pad4)") (class "Default")
      (node (ref "CON202") (pin "4") (pinfunction "NC_4") (pintype "passive+no_connect"))
    )
    (net (code "75") (name "unconnected-(U203-ACBUS0-Pad15)") (class "Default")
      (node (ref "U203") (pin "15") (pinfunction "ACBUS0_15") (pintype "bidirectional+no_connect"))
    )
    (net (code "76") (name "unconnected-(U203-ACBUS1-Pad13)") (class "Default")
      (node (ref "U203") (pin "13") (pinfunction "ACBUS1_13") (pintype "bidirectional+no_connect"))
    )
    (net (code "77") (name "unconnected-(U203-ACBUS2-Pad12)") (class "Default")
      (node (ref "U203") (pin "12") (pinfunction "ACBUS2_12") (pintype "bidirectional+no_connect"))
    )
    (net (code "78") (name "unconnected-(U203-ACBUS3-Pad11)") (class "Default")
      (node (ref "U203") (pin "11") (pinfunction "ACBUS3_11") (pintype "bidirectional+no_connect"))
    )
    (net (code "79") (name "unconnected-(U203-ADBUS6-Pad17)") (class "Default")
      (node (ref "U203") (pin "17") (pinfunction "ADBUS6_17") (pintype "bidirectional+no_connect"))
    )
    (net (code "80") (name "unconnected-(U203-ADBUS7-Pad16)") (class "Default")
      (node (ref "U203") (pin "16") (pinfunction "ADBUS7_16") (pintype "bidirectional+no_connect"))
    )
    (net (code "81") (name "unconnected-(U203-BCBUS0-Pad30)") (class "Default")
      (node (ref "U203") (pin "30") (pinfunction "BCBUS0_30") (pintype "bidirectional+no_connect"))
    )
    (net (code "82") (name "unconnected-(U203-BCBUS1-Pad29)") (class "Default")
      (node (ref "U203") (pin "29") (pinfunction "BCBUS1_29") (pintype "bidirectional+no_connect"))
    )
    (net (code "83") (name "unconnected-(U203-BCBUS2-Pad28)") (class "Default")
      (node (ref "U203") (pin "28") (pinfunction "BCBUS2_28") (pintype "bidirectional+no_connect"))
    )
    (net (code "84") (name "unconnected-(U203-BCBUS3-Pad27)") (class "Default")
      (node (ref "U203") (pin "27") (pinfunction "BCBUS3_27") (pintype "bidirectional+no_connect"))
    )
    (net (code "85") (name "unconnected-(U203-BDBUS2-Pad38)") (class "Default")
      (node (ref "U203") (pin "38") (pinfunction "BDBUS2_38") (pintype "bidirectional+no_connect"))
    )
    (net (code "86") (name "unconnected-(U203-BDBUS3-Pad37)") (class "Default")
      (node (ref "U203") (pin "37") (pinfunction "BDBUS3_37") (pintype "bidirectional+no_connect"))
    )
    (net (code "87") (name "unconnected-(U203-BDBUS4-Pad36)") (class "Default")
      (node (ref "U203") (pin "36") (pinfunction "BDBUS4_36") (pintype "bidirectional+no_connect"))
    )
    (net (code "88") (name "unconnected-(U203-BDBUS5-Pad35)") (class "Default")
      (node (ref "U203") (pin "35") (pinfunction "BDBUS5_35") (pintype "bidirectional+no_connect"))
    )
    (net (code "89") (name "unconnected-(U203-BDBUS6-Pad33)") (class "Default")
      (node (ref "U203") (pin "33") (pinfunction "BDBUS6_33") (pintype "bidirectional+no_connect"))
    )
    (net (code "90") (name "unconnected-(U203-BDBUS7-Pad32)") (class "Default")
      (node (ref "U203") (pin "32") (pinfunction "BDBUS7_32") (pintype "bidirectional+no_connect"))
    )
    (net (code "91") (name "unconnected-(U203-~{PWREN}-Pad41)") (class "Default")
      (node (ref "U203") (pin "41") (pinfunction "~{PWREN}_41") (pintype "output+no_connect"))
    )
    (net (code "92") (name "unconnected-(U204-DIN2-Pad10)") (class "Default")
      (node (ref "U204") (pin "10") (pinfunction "DIN2_10") (pintype "input+no_connect"))
    )
    (net (code "93") (name "unconnected-(U204-DOUT2-Pad7)") (class "Default")
      (node (ref "U204") (pin "7") (pinfunction "DOUT2_7") (pintype "output+no_connect"))
    )
    (net (code "94") (name "unconnected-(U204-RIN2-Pad8)") (class "Default")
      (node (ref "U204") (pin "8") (pinfunction "RIN2_8") (pintype "input+no_connect"))
    )
    (net (code "95") (name "unconnected-(U204-ROUT2-Pad9)") (class "Default")
      (node (ref "U204") (pin "9") (pinfunction "ROUT2_9") (pintype "output+no_connect"))
    )
    (net (code "96") (name "unconnected-(U205-NC-Pad7)") (class "Default")
      (node (ref "U205") (pin "7") (pinfunction "NC_7") (pintype "passive+no_connect"))
    )
    (net (code "97") (name "unconnected-(U206-DAT1-Pad8)") (class "Default")
      (node (ref "U206") (pin "8") (pinfunction "DAT1_8") (pintype "passive+no_connect"))
    )
    (net (code "98") (name "unconnected-(U206-DAT2-Pad1)") (class "Default")
      (node (ref "U206") (pin "1") (pinfunction "DAT2_1") (pintype "passive+no_connect"))
    )
  )
)
